# main.net
KiCad netlist of a schematic drawn in EAGLE
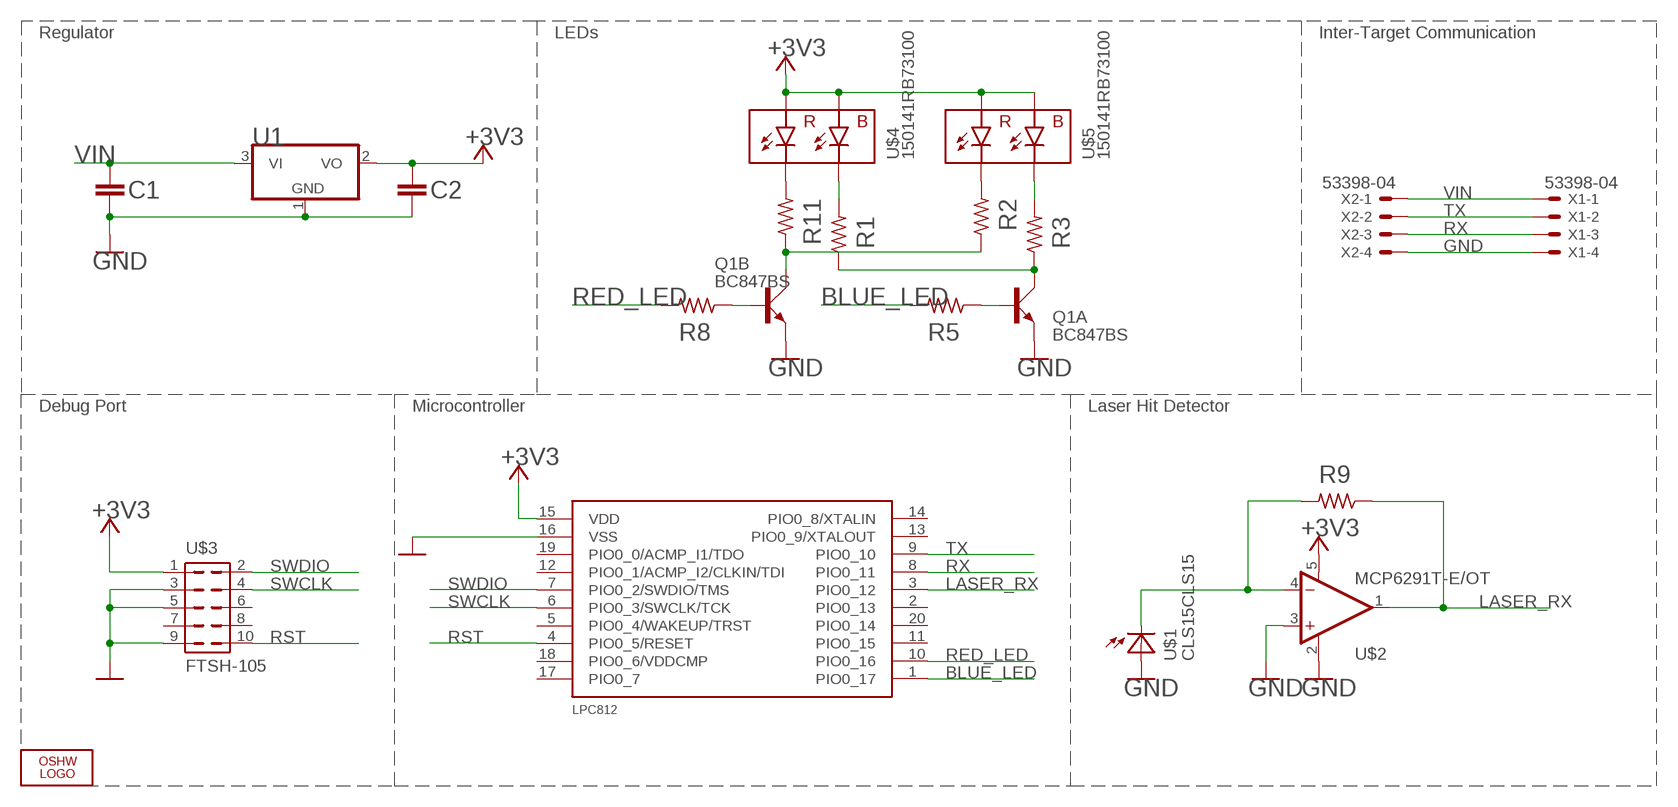
[diagram p0: schematic, sheet 1]

(export (version "E")
  (design (tool "Eeschema 10.0.6"))
  (components
    (comp (ref "C1")
      (value "C1608X5R1C106M080AB")
      (footprint "eagle-import:0603-CAP")
      (libsource (lib "eagle-import") (part "CAP0603-CAP"))
    )
    (comp (ref "C2")
      (value "C1608X5R1C106M080AB")
      (footprint "eagle-import:0603-CAP")
      (libsource (lib "eagle-import") (part "CAP0603-CAP"))
    )
    (comp (ref "LOGO2")
      (value "OSHW_LOGO_FILLX0150-NT")
      (footprint "eagle-import:OSHW_FILLX150_NOTEXT")
      (libsource (lib "eagle-import") (part "OSHW_LOGO_FILLX0150-NT"))
    )
    (comp (ref "LPC812")
      (value "LPC812M101JDH20")
      (footprint "eagle-import:TSSOP20")
      (libsource (lib "eagle-import") (part "LPC812M101JDH20"))
    )
    (comp (ref "Q1")
      (value "BC847BS")
      (footprint "eagle-import:SOT363_PHILIPS")
      (libsource (lib "eagle-import") (part "BC847BS"))
    )
    (comp (ref "R1")
      (value "CRCW0603200RFKEA")
      (footprint "eagle-import:R0603")
      (libsource (lib "eagle-import") (part "R-US_R0603"))
    )
    (comp (ref "R2")
      (value "CRCW0603200RFKEA")
      (footprint "eagle-import:R0603")
      (libsource (lib "eagle-import") (part "R-US_R0603"))
    )
    (comp (ref "R3")
      (value "CRCW0603200RFKEA")
      (footprint "eagle-import:R0603")
      (libsource (lib "eagle-import") (part "R-US_R0603"))
    )
    (comp (ref "R5")
      (value "CRCW0603200RFKEA")
      (footprint "eagle-import:R0603")
      (libsource (lib "eagle-import") (part "R-US_R0603"))
    )
    (comp (ref "R8")
      (value "CRCW0603200RFKEA")
      (footprint "eagle-import:R0603")
      (libsource (lib "eagle-import") (part "R-US_R0603"))
    )
    (comp (ref "R9")
      (value "CRCW0603200RFKEA")
      (footprint "eagle-import:R0603")
      (libsource (lib "eagle-import") (part "R-US_R0603"))
    )
    (comp (ref "R11")
      (value "CRCW0603200RFKEA")
      (footprint "eagle-import:R0603")
      (libsource (lib "eagle-import") (part "R-US_R0603"))
    )
    (comp (ref "U$1")
      (value "CLS15CLS15")
      (footprint "eagle-import:CLS15")
      (libsource (lib "eagle-import") (part "CLS15CLS15"))
    )
    (comp (ref "U$2")
      (value "MCP6291T-E/OT")
      (footprint "eagle-import:SOT23-5")
      (libsource (lib "eagle-import") (part "MCP6291T-E/OT"))
    )
    (comp (ref "U$3")
      (value "FTSH-105")
      (footprint "eagle-import:FTSH-105-01-XXX-DV-K")
      (libsource (lib "eagle-import") (part "FTSH-105"))
    )
    (comp (ref "U$4")
      (value "150141RB73100")
      (footprint "eagle-import:150141RB")
      (libsource (lib "eagle-import") (part "LED_RB"))
    )
    (comp (ref "U$5")
      (value "150141RB73100")
      (footprint "eagle-import:150141RB")
      (libsource (lib "eagle-import") (part "LED_RB"))
    )
    (comp (ref "U1")
      (value "MCP1703T-3002E/CB")
      (footprint "eagle-import:SOT23")
      (libsource (lib "eagle-import") (part "MCP1703CB"))
    )
    (comp (ref "X1")
      (value "53398-04")
      (footprint "eagle-import:53398-04")
      (libsource (lib "eagle-import") (part "53?-04398"))
    )
    (comp (ref "X2")
      (value "53398-04")
      (footprint "eagle-import:53398-04")
      (libsource (lib "eagle-import") (part "53?-04398"))
    )
  )
  (nets
    (net (code "1") (name "+3V3") (class "Default")
      (node (ref "C2") (pin "1") (pinfunction "1_1") (pintype "passive"))
      (node (ref "LPC812") (pin "15") (pinfunction "VDD_15") (pintype "bidirectional"))
      (node (ref "U$2") (pin "5") (pinfunction "V+_5") (pintype "power_in"))
      (node (ref "U$3") (pin "1") (pinfunction "1_1") (pintype "passive"))
      (node (ref "U$4") (pin "1") (pinfunction "1_1") (pintype "passive"))
      (node (ref "U$4") (pin "2") (pinfunction "2_2") (pintype "passive"))
      (node (ref "U$5") (pin "1") (pinfunction "1_1") (pintype "passive"))
      (node (ref "U$5") (pin "2") (pinfunction "2_2") (pintype "passive"))
      (node (ref "U1") (pin "2") (pinfunction "VO_2") (pintype "passive"))
    )
    (net (code "2") (name "/BLUE_LED") (class "Default")
      (node (ref "LPC812") (pin "1") (pinfunction "PIO0_17_1") (pintype "bidirectional"))
      (node (ref "R5") (pin "2") (pinfunction "2_2") (pintype "passive"))
    )
    (net (code "3") (name "/LASER_RX") (class "Default")
      (node (ref "LPC812") (pin "3") (pinfunction "PIO0_12_3") (pintype "bidirectional"))
      (node (ref "R9") (pin "1") (pinfunction "1_1") (pintype "passive"))
      (node (ref "U$2") (pin "1") (pinfunction "OUT_1") (pintype "output"))
    )
    (net (code "4") (name "/RED_LED") (class "Default")
      (node (ref "LPC812") (pin "10") (pinfunction "PIO0_16_10") (pintype "bidirectional"))
      (node (ref "R8") (pin "2") (pinfunction "2_2") (pintype "passive"))
    )
    (net (code "5") (name "/RST") (class "Default")
      (node (ref "LPC812") (pin "4") (pinfunction "PIO0_5/RESET_4") (pintype "bidirectional"))
      (node (ref "U$3") (pin "10") (pinfunction "10_10") (pintype "passive"))
    )
    (net (code "6") (name "/RX") (class "Default")
      (node (ref "LPC812") (pin "8") (pinfunction "PIO0_11_8") (pintype "bidirectional"))
      (node (ref "X1") (pin "3") (pinfunction "S_3") (pintype "passive"))
      (node (ref "X2") (pin "3") (pinfunction "S_3") (pintype "passive"))
    )
    (net (code "7") (name "/SWCLK") (class "Default")
      (node (ref "LPC812") (pin "6") (pinfunction "PIO0_3/SWCLK/TCK_6") (pintype "bidirectional"))
      (node (ref "U$3") (pin "4") (pinfunction "4_4") (pintype "passive"))
    )
    (net (code "8") (name "/SWDIO") (class "Default")
      (node (ref "LPC812") (pin "7") (pinfunction "PIO0_2/SWDIO/TMS_7") (pintype "bidirectional"))
      (node (ref "U$3") (pin "2") (pinfunction "2_2") (pintype "passive"))
    )
    (net (code "9") (name "/TX") (class "Default")
      (node (ref "LPC812") (pin "9") (pinfunction "PIO0_10_9") (pintype "bidirectional"))
      (node (ref "X1") (pin "2") (pinfunction "S_2") (pintype "passive"))
      (node (ref "X2") (pin "2") (pinfunction "S_2") (pintype "passive"))
    )
    (net (code "10") (name "/VIN") (class "Default")
      (node (ref "C1") (pin "1") (pinfunction "1_1") (pintype "passive"))
      (node (ref "U1") (pin "3") (pinfunction "VI_3") (pintype "input"))
      (node (ref "X1") (pin "1") (pinfunction "S_1") (pintype "passive"))
      (node (ref "X2") (pin "1") (pinfunction "S_1") (pintype "passive"))
    )
    (net (code "11") (name "GND") (class "Default")
      (node (ref "C1") (pin "2") (pinfunction "2_2") (pintype "passive"))
      (node (ref "C2") (pin "2") (pinfunction "2_2") (pintype "passive"))
      (node (ref "LPC812") (pin "16") (pinfunction "VSS_16") (pintype "bidirectional"))
      (node (ref "Q1") (pin "1") (pinfunction "E_1") (pintype "passive"))
      (node (ref "Q1") (pin "4") (pinfunction "E_4") (pintype "passive"))
      (node (ref "U$1") (pin "1") (pinfunction "A_1") (pintype "passive"))
      (node (ref "U$1") (pin "2") (pinfunction "A_2") (pintype "passive"))
      (node (ref "U$2") (pin "2") (pinfunction "V-_2") (pintype "power_in"))
      (node (ref "U$2") (pin "3") (pinfunction "+IN_3") (pintype "input"))
      (node (ref "U$3") (pin "3") (pinfunction "3_3") (pintype "passive"))
      (node (ref "U$3") (pin "5") (pinfunction "5_5") (pintype "passive"))
      (node (ref "U$3") (pin "9") (pinfunction "9_9") (pintype "passive"))
      (node (ref "U1") (pin "1") (pinfunction "GND_1") (pintype "passive"))
      (node (ref "X1") (pin "4") (pinfunction "S_4") (pintype "passive"))
      (node (ref "X2") (pin "4") (pinfunction "S_4") (pintype "passive"))
    )
    (net (code "12") (name "Net-(Q1A-B)") (class "Default")
      (node (ref "Q1") (pin "2") (pinfunction "B_2") (pintype "passive"))
      (node (ref "R5") (pin "1") (pinfunction "1_1") (pintype "passive"))
    )
    (net (code "13") (name "Net-(Q1A-C)") (class "Default")
      (node (ref "Q1") (pin "6") (pinfunction "C_6") (pintype "passive"))
      (node (ref "R1") (pin "1") (pinfunction "1_1") (pintype "passive"))
      (node (ref "R3") (pin "1") (pinfunction "1_1") (pintype "passive"))
    )
    (net (code "14") (name "Net-(Q1B-B)") (class "Default")
      (node (ref "Q1") (pin "5") (pinfunction "B_5") (pintype "passive"))
      (node (ref "R8") (pin "1") (pinfunction "1_1") (pintype "passive"))
    )
    (net (code "15") (name "Net-(Q1B-C)") (class "Default")
      (node (ref "Q1") (pin "3") (pinfunction "C_3") (pintype "passive"))
      (node (ref "R11") (pin "1") (pinfunction "1_1") (pintype "passive"))
      (node (ref "R2") (pin "1") (pinfunction "1_1") (pintype "passive"))
    )
    (net (code "16") (name "Net-(R1-Pad2)") (class "Default")
      (node (ref "R1") (pin "2") (pinfunction "2_2") (pintype "passive"))
      (node (ref "U$4") (pin "4") (pinfunction "4_4") (pintype "passive"))
    )
    (net (code "17") (name "Net-(R2-Pad2)") (class "Default")
      (node (ref "R2") (pin "2") (pinfunction "2_2") (pintype "passive"))
      (node (ref "U$5") (pin "3") (pinfunction "3_3") (pintype "passive"))
    )
    (net (code "18") (name "Net-(R3-Pad2)") (class "Default")
      (node (ref "R3") (pin "2") (pinfunction "2_2") (pintype "passive"))
      (node (ref "U$5") (pin "4") (pinfunction "4_4") (pintype "passive"))
    )
    (net (code "19") (name "Net-(R11-Pad2)") (class "Default")
      (node (ref "R11") (pin "2") (pinfunction "2_2") (pintype "passive"))
      (node (ref "U$4") (pin "3") (pinfunction "3_3") (pintype "passive"))
    )
    (net (code "20") (name "Net-(U$2--IN)") (class "Default")
      (node (ref "R9") (pin "2") (pinfunction "2_2") (pintype "passive"))
      (node (ref "U$1") (pin "3") (pinfunction "C_3") (pintype "passive"))
      (node (ref "U$1") (pin "4") (pinfunction "C_4") (pintype "passive"))
      (node (ref "U$2") (pin "4") (pinfunction "-IN_4") (pintype "input"))
    )
    (net (code "21") (name "unconnected-(LPC812-PIO0_0{slash}ACMP_I1{slash}TDO-Pad19)") (class "Default")
      (node (ref "LPC812") (pin "19") (pinfunction "PIO0_0/ACMP_I1/TDO_19") (pintype "bidirectional"))
    )
    (net (code "22") (name "unconnected-(LPC812-PIO0_1{slash}ACMP_I2{slash}CLKIN{slash}TDI-Pad12)") (class "Default")
      (node (ref "LPC812") (pin "12") (pinfunction "PIO0_1/ACMP_I2/CLKIN/TDI_12") (pintype "bidirectional"))
    )
    (net (code "23") (name "unconnected-(LPC812-PIO0_4{slash}WAKEUP{slash}TRST-Pad5)") (class "Default")
      (node (ref "LPC812") (pin "5") (pinfunction "PIO0_4/WAKEUP/TRST_5") (pintype "bidirectional"))
    )
    (net (code "24") (name "unconnected-(LPC812-PIO0_6{slash}VDDCMP-Pad18)") (class "Default")
      (node (ref "LPC812") (pin "18") (pinfunction "PIO0_6/VDDCMP_18") (pintype "bidirectional"))
    )
    (net (code "25") (name "unconnected-(LPC812-PIO0_7-Pad17)") (class "Default")
      (node (ref "LPC812") (pin "17") (pinfunction "PIO0_7_17") (pintype "bidirectional"))
    )
    (net (code "26") (name "unconnected-(LPC812-PIO0_8{slash}XTALIN-Pad14)") (class "Default")
      (node (ref "LPC812") (pin "14") (pinfunction "PIO0_8/XTALIN_14") (pintype "bidirectional"))
    )
    (net (code "27") (name "unconnected-(LPC812-PIO0_9{slash}XTALOUT-Pad13)") (class "Default")
      (node (ref "LPC812") (pin "13") (pinfunction "PIO0_9/XTALOUT_13") (pintype "bidirectional"))
    )
    (net (code "28") (name "unconnected-(LPC812-PIO0_13-Pad2)") (class "Default")
      (node (ref "LPC812") (pin "2") (pinfunction "PIO0_13_2") (pintype "bidirectional"))
    )
    (net (code "29") (name "unconnected-(LPC812-PIO0_14-Pad20)") (class "Default")
      (node (ref "LPC812") (pin "20") (pinfunction "PIO0_14_20") (pintype "bidirectional"))
    )
    (net (code "30") (name "unconnected-(LPC812-PIO0_15-Pad11)") (class "Default")
      (node (ref "LPC812") (pin "11") (pinfunction "PIO0_15_11") (pintype "bidirectional"))
    )
    (net (code "31") (name "unconnected-(U$3-Pad6)") (class "Default")
      (node (ref "U$3") (pin "6") (pinfunction "6_6") (pintype "passive"))
    )
    (net (code "32") (name "unconnected-(U$3-Pad7)") (class "Default")
      (node (ref "U$3") (pin "7") (pinfunction "7_7") (pintype "passive"))
    )
    (net (code "33") (name "unconnected-(U$3-Pad8)") (class "Default")
      (node (ref "U$3") (pin "8") (pinfunction "8_8") (pintype "passive"))
    )
  )
)
